# Main.net
KiCad netlist of a schematic drawn in Altium Designer
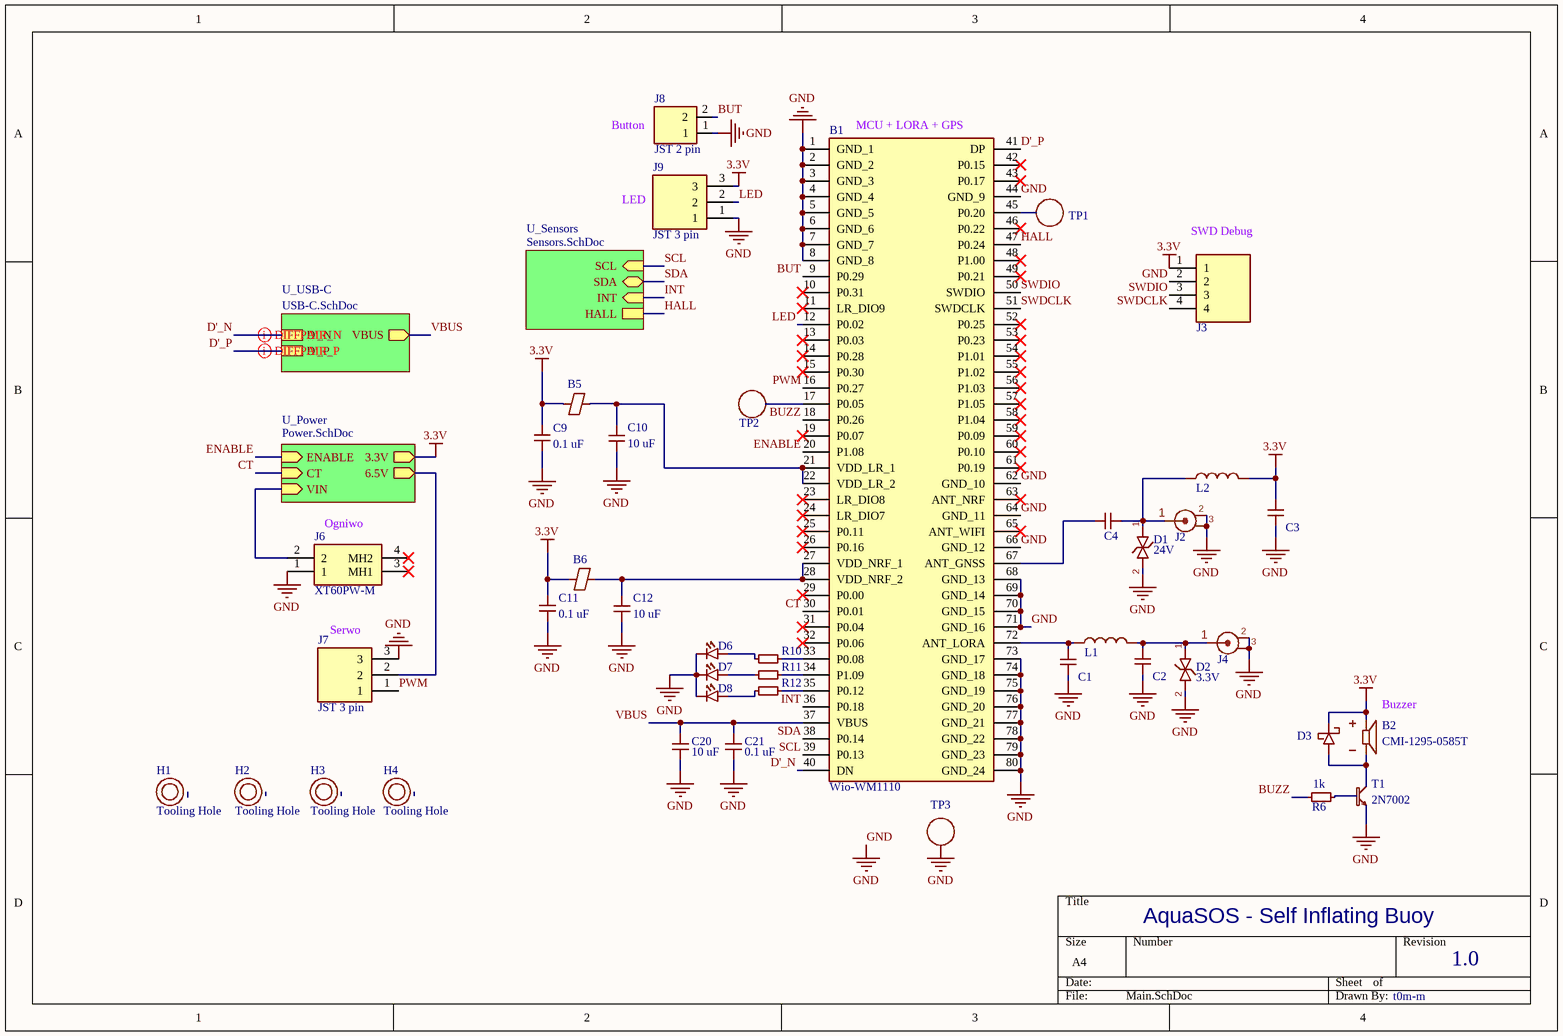
[diagram p0: Main.SchDoc]

(export (version "E")
  (design (tool "Eeschema 10.0.6"))
  (components
    (comp (ref "B1")
      (value "Wio-WM1110")
      (footprint "WioWM1110")
      (description "LoRa Wireless Module - Powered by Semtech")
      (libsource (lib "Schlib1") (part "Wio-WM1110"))
    )
    (comp (ref "B2")
      (value "CMI-1295-0585T")
      (footprint "CMI-1295-0585T")
      (description "Buzzer")
      (libsource (lib "Schlib1") (part "CMI-1295-0585T"))
    )
    (comp (ref "B5")
      (value "MPZ1608S121ATDH5")
      (footprint "MPZ1608S121ATDH5")
      (description "Ferrite Beads 0603 120ohms 2000mA Power Line AEC-Q200")
      (fields (field (name "MOUSER PART NUMBER") "810-MPZ1608S121ATDH5"))
      (libsource (lib "Schlib1") (part "MPZ1608S121ATDH5"))
    )
    (comp (ref "B6")
      (value "MPZ1608S121ATDH5")
      (footprint "MPZ1608S121ATDH5")
      (description "Ferrite Beads 0603 120ohms 2000mA Power Line AEC-Q200")
      (fields (field (name "MOUSER PART NUMBER") "810-MPZ1608S121ATDH5"))
      (libsource (lib "Schlib1") (part "MPZ1608S121ATDH5"))
    )
    (comp (ref "C1")
      (value "Capacitor")
      (footprint "KGM05CS60J106MH")
      (description "0402 SMD")
      (libsource (lib "AquaSOS DevBoard") (part "Capacitor"))
    )
    (comp (ref "C2")
      (value "Capacitor")
      (footprint "KGM05CS60J106MH")
      (description "0402 SMD")
      (libsource (lib "AquaSOS DevBoard") (part "Capacitor"))
    )
    (comp (ref "C3")
      (value "Capacitor")
      (footprint "KGM05CS60J106MH")
      (description "0402 SMD")
      (libsource (lib "AquaSOS DevBoard") (part "Capacitor"))
    )
    (comp (ref "C4")
      (value "Capacitor")
      (footprint "KGM05CS60J106MH")
      (description "0402 SMD")
      (libsource (lib "AquaSOS DevBoard") (part "Capacitor"))
    )
    (comp (ref "C9")
      (value "0.1 uF")
      (footprint "MLASU105SB7104KFNB25")
      (description "0.1uF Capacitor")
      (libsource (lib "Schlib1") (part "MLASU105SB7104KFNB25"))
    )
    (comp (ref "C10")
      (value "10 uF")
      (footprint "KGM05CS60J106MH")
      (description "10 uF Capacitor")
      (libsource (lib "Schlib1") (part "KGM05CS60J106MH"))
    )
    (comp (ref "C11")
      (value "0.1 uF")
      (footprint "MLASU105SB7104KFNB25")
      (description "0.1uF Capacitor")
      (libsource (lib "Schlib1") (part "MLASU105SB7104KFNB25"))
    )
    (comp (ref "C12")
      (value "10 uF")
      (footprint "KGM05CS60J106MH")
      (description "10 uF Capacitor")
      (libsource (lib "Schlib1") (part "KGM05CS60J106MH"))
    )
    (comp (ref "C20")
      (value "10 uF")
      (footprint "KGM05CS60J106MH")
      (description "10 uF Capacitor")
      (libsource (lib "AquaSOS DevBoard") (part "KGM05CS60J106MH"))
    )
    (comp (ref "C21")
      (value "0.1 uF")
      (footprint "MLASU105SB7104KFNB25")
      (description "0.1uF Capacitor")
      (libsource (lib "AquaSOS DevBoard") (part "MLASU105SB7104KFNB25"))
    )
    (comp (ref "D1")
      (value "24V")
      (footprint "RCLAMP2431TTCT")
      (description "ESD Suppressors / TVS Diodes LOW CAP/ESD CLAP, 1 LINE")
      (fields
        (field (name "MOUSER PART NUMBER") "947-RCLAMP2431T.TCT")
        (field (name "MANUFACTURER_PART_NUMBER") "RCLAMP2431T.TCT")
      )
      (libsource (lib "Schlib1") (part "RCLAMP2431T.TCT"))
    )
    (comp (ref "D2")
      (value "CPDV3V3A-HF")
      (footprint "CPDV3V3A-HF")
      (description "3.3 V, 0.4pF, Bidirectional")
      (libsource (lib "AquaSOS DevBoard") (part "CPDV3V3A-HF"))
    )
    (comp (ref "D3")
      (value "BAT5402VH6327XTSA1")
      (footprint "BAT5402VH6327XTSA1")
      (description "Schottky Diode")
      (libsource (lib "Schlib1") (part "BAT5402VH6327XTSA1"))
    )
    (comp (ref "D6")
      (value "APT1608SGC")
      (footprint "APT1608SGC")
      (description "0402 SMD LED")
      (libsource (lib "AquaSOS DevBoard") (part "APT1608SGC"))
    )
    (comp (ref "D7")
      (value "APT1608SGC")
      (footprint "APT1608SGC")
      (description "0402 SMD LED")
      (libsource (lib "AquaSOS DevBoard") (part "APT1608SGC"))
    )
    (comp (ref "D8")
      (value "APT1608SGC")
      (footprint "APT1608SGC")
      (description "0402 SMD LED")
      (libsource (lib "AquaSOS DevBoard") (part "APT1608SGC"))
    )
    (comp (ref "H1")
      (value "Tooling Hole")
      (footprint "Tooling Hole")
      (libsource (lib "AquaSOS DevBoard") (part "Tooling Hole"))
    )
    (comp (ref "H2")
      (value "Tooling Hole")
      (footprint "Tooling Hole")
      (libsource (lib "AquaSOS DevBoard") (part "Tooling Hole"))
    )
    (comp (ref "H3")
      (value "Tooling Hole")
      (footprint "Tooling Hole")
      (libsource (lib "AquaSOS DevBoard") (part "Tooling Hole"))
    )
    (comp (ref "H4")
      (value "Tooling Hole")
      (footprint "Tooling Hole")
      (libsource (lib "AquaSOS DevBoard") (part "Tooling Hole"))
    )
    (comp (ref "J2")
      (value "U.FL-R-SMT-1(10)")
      (footprint "HRS_U.FL-R-SMT-1(10)")
      (description "Antenna Connector")
      (libsource (lib "AquaSOS DevBoard") (part "U.FL-R-SMT-1(10)"))
    )
    (comp (ref "J3")
      (value "22-10-2041")
      (footprint "1x4 Goldpin Header")
      (description "Headers & Wire Housings VERT PCB HDR 4P GOLD PLATING")
      (fields (field (name "MOUSER PART NUMBER") "538-22-10-2041"))
      (libsource (lib "Schlib1") (part "1x4 Goldpin Header"))
    )
    (comp (ref "J4")
      (value "U.FL-R-SMT-1(10)")
      (footprint "HRS_U.FL-R-SMT-1(10)")
      (description "Antenna Connector")
      (libsource (lib "AquaSOS DevBoard") (part "U.FL-R-SMT-1(10)"))
    )
    (comp (ref "J6")
      (value "XT60PW-M")
      (footprint "XT60PWM")
      (description "Connector: DC supply; socket; XT60; male; PIN: 2; on PCBs; THT; 30A")
      (libsource (lib "Schlib1") (part "XT60PW-M"))
    )
    (comp (ref "J7")
      (value "JST 3 pin")
      (footprint "S3B-PH-K-S")
      (description "JST 3 pin connector")
      (libsource (lib "AquaSOS DevBoard") (part "JST 3 pin"))
    )
    (comp (ref "J8")
      (value "JST 2 pin")
      (footprint "JST_S2B-PH-K-S(LF)(SN)")
      (description "Connector Header Through Hole, Right Angle 2 position")
      (fields (field (name "MF") "JST Sales America Inc.") (field (name "MP") "S2B-PH-K-S(LF)(SN)"))
      (libsource (lib "AquaSOS DevBoard") (part "JST 2 pin"))
    )
    (comp (ref "J9")
      (value "JST 3 pin")
      (footprint "S3B-PH-K-S")
      (description "JST 3 pin connector")
      (libsource (lib "AquaSOS DevBoard") (part "JST 3 pin"))
    )
    (comp (ref "L1")
      (value "Inductor")
      (footprint "KGM05CS60J106MH")
      (libsource (lib "AquaSOS DevBoard") (part "Inductor"))
    )
    (comp (ref "L2")
      (value "Inductor")
      (footprint "KGM05CS60J106MH")
      (libsource (lib "AquaSOS DevBoard") (part "Inductor"))
    )
    (comp (ref "R6")
      (value "MR04X102 JTL")
      (footprint "MR04X102 JTL")
      (description "1k 0402 Resistor")
      (libsource (lib "Schlib1") (part "MR04X102 JTL"))
    )
    (comp (ref "R10")
      (value "300")
      (footprint "RC0402JR-075K1P")
      (libsource (lib "AquaSOS DevBoard") (part "CR0402-FX-3000GLF"))
    )
    (comp (ref "R11")
      (value "300")
      (footprint "RC0402JR-075K1P")
      (libsource (lib "AquaSOS DevBoard") (part "CR0402-FX-3000GLF"))
    )
    (comp (ref "R12")
      (value "300")
      (footprint "RC0402JR-075K1P")
      (libsource (lib "AquaSOS DevBoard") (part "CR0402-FX-3000GLF"))
    )
    (comp (ref "T1")
      (value "2N7002")
      (footprint "2N7002")
      (description "Transistor")
      (libsource (lib "Schlib1") (part "2N7002"))
    )
    (comp (ref "TP1")
      (value "TP")
      (footprint "Test Point")
      (description "Test Point")
      (libsource (lib "AquaSOS DevBoard") (part "Test Point"))
    )
    (comp (ref "TP2")
      (value "TP")
      (footprint "Test Point")
      (description "Test Point")
      (libsource (lib "AquaSOS DevBoard") (part "Test Point"))
    )
    (comp (ref "TP3")
      (value "TP")
      (footprint "Test Point")
      (description "Test Point")
      (libsource (lib "AquaSOS DevBoard") (part "Test Point"))
    )
  )
  (nets
    (net (code "1") (name "/6.5V") (class "Default")
      (node (ref "J7") (pin "2") (pinfunction "2_2") (pintype "passive"))
    )
    (net (code "2") (name "/BUT") (class "Default")
      (node (ref "B1") (pin "9") (pinfunction "P0.29_9") (pintype "passive"))
      (node (ref "J8") (pin "2") (pinfunction "2_2") (pintype "passive"))
    )
    (net (code "3") (name "/BUZZ") (class "Default")
      (node (ref "B1") (pin "18") (pinfunction "P0.26_18") (pintype "passive"))
      (node (ref "R6") (pin "1") (pinfunction "1_1") (pintype "passive"))
    )
    (net (code "4") (name "/CT") (class "Default")
      (node (ref "B1") (pin "30") (pinfunction "P0.01_30") (pintype "passive"))
    )
    (net (code "5") (name "/D'_N") (class "Default")
      (node (ref "B1") (pin "40") (pinfunction "DN_40") (pintype "passive"))
    )
    (net (code "6") (name "/D'_P") (class "Default")
      (node (ref "B1") (pin "41") (pinfunction "DP_41") (pintype "passive"))
    )
    (net (code "7") (name "/ENABLE") (class "Default")
      (node (ref "B1") (pin "20") (pinfunction "P1.08_20") (pintype "passive"))
    )
    (net (code "8") (name "/HALL") (class "Default")
      (node (ref "B1") (pin "47") (pinfunction "P0.24_47") (pintype "passive"))
    )
    (net (code "9") (name "/INT") (class "Default")
      (node (ref "B1") (pin "36") (pinfunction "P0.18_36") (pintype "passive"))
    )
    (net (code "10") (name "/LED") (class "Default")
      (node (ref "B1") (pin "12") (pinfunction "P0.02_12") (pintype "passive"))
      (node (ref "J9") (pin "2") (pinfunction "2_2") (pintype "passive"))
    )
    (net (code "11") (name "/PWM") (class "Default")
      (node (ref "B1") (pin "16") (pinfunction "P0.27_16") (pintype "passive"))
      (node (ref "J7") (pin "1") (pinfunction "1_1") (pintype "passive"))
    )
    (net (code "12") (name "/SCL") (class "Default")
      (node (ref "B1") (pin "39") (pinfunction "P0.13_39") (pintype "passive"))
    )
    (net (code "13") (name "/SDA") (class "Default")
      (node (ref "B1") (pin "38") (pinfunction "P0.14_38") (pintype "passive"))
    )
    (net (code "14") (name "/SWDCLK") (class "Default")
      (node (ref "B1") (pin "51") (pinfunction "SWDCLK_51") (pintype "passive"))
      (node (ref "J3") (pin "4") (pinfunction "4_4") (pintype "passive"))
    )
    (net (code "15") (name "/SWDIO") (class "Default")
      (node (ref "B1") (pin "50") (pinfunction "SWDIO_50") (pintype "passive"))
      (node (ref "J3") (pin "3") (pinfunction "3_3") (pintype "passive"))
    )
    (net (code "16") (name "/VBUS") (class "Default")
      (node (ref "B1") (pin "37") (pinfunction "VBUS_37") (pintype "passive"))
      (node (ref "C20") (pin "1") (pinfunction "1_1") (pintype "passive"))
      (node (ref "C21") (pin "1") (pinfunction "1_1") (pintype "passive"))
    )
    (net (code "17") (name "/VIN") (class "Default")
      (node (ref "J6") (pin "2") (pinfunction "2_2") (pintype "passive"))
    )
    (net (code "18") (name "3.3V") (class "Default")
      (node (ref "B2") (pin "P") (pinfunction "P_P") (pintype "passive"))
      (node (ref "B5") (pin "1") (pinfunction "1_1") (pintype "passive"))
      (node (ref "B6") (pin "1") (pinfunction "1_1") (pintype "passive"))
      (node (ref "C11") (pin "1") (pinfunction "1_1") (pintype "passive"))
      (node (ref "C3") (pin "1") (pinfunction "1_1") (pintype "passive"))
      (node (ref "C9") (pin "1") (pinfunction "1_1") (pintype "passive"))
      (node (ref "D3") (pin "2") (pinfunction "A_2") (pintype "passive"))
      (node (ref "J3") (pin "1") (pinfunction "1_1") (pintype "passive"))
      (node (ref "J9") (pin "3") (pinfunction "3_3") (pintype "passive"))
      (node (ref "L2") (pin "2") (pinfunction "2_2") (pintype "passive"))
    )
    (net (code "19") (name "GND") (class "Default")
      (node (ref "B1") (pin "1") (pinfunction "GND_1_1") (pintype "passive"))
      (node (ref "B1") (pin "2") (pinfunction "GND_2_2") (pintype "passive"))
      (node (ref "B1") (pin "3") (pinfunction "GND_3_3") (pintype "passive"))
      (node (ref "B1") (pin "4") (pinfunction "GND_4_4") (pintype "passive"))
      (node (ref "B1") (pin "44") (pinfunction "GND_9_44") (pintype "passive"))
      (node (ref "B1") (pin "5") (pinfunction "GND_5_5") (pintype "passive"))
      (node (ref "B1") (pin "6") (pinfunction "GND_6_6") (pintype "passive"))
      (node (ref "B1") (pin "62") (pinfunction "GND_10_62") (pintype "passive"))
      (node (ref "B1") (pin "64") (pinfunction "GND_11_64") (pintype "passive"))
      (node (ref "B1") (pin "66") (pinfunction "GND_12_66") (pintype "passive"))
      (node (ref "B1") (pin "68") (pinfunction "GND_13_68") (pintype "passive"))
      (node (ref "B1") (pin "69") (pinfunction "GND_14_69") (pintype "passive"))
      (node (ref "B1") (pin "7") (pinfunction "GND_7_7") (pintype "passive"))
      (node (ref "B1") (pin "70") (pinfunction "GND_15_70") (pintype "passive"))
      (node (ref "B1") (pin "71") (pinfunction "GND_16_71") (pintype "passive"))
      (node (ref "B1") (pin "73") (pinfunction "GND_17_73") (pintype "passive"))
      (node (ref "B1") (pin "74") (pinfunction "GND_18_74") (pintype "passive"))
      (node (ref "B1") (pin "75") (pinfunction "GND_19_75") (pintype "passive"))
      (node (ref "B1") (pin "76") (pinfunction "GND_20_76") (pintype "passive"))
      (node (ref "B1") (pin "77") (pinfunction "GND_21_77") (pintype "passive"))
      (node (ref "B1") (pin "78") (pinfunction "GND_22_78") (pintype "passive"))
      (node (ref "B1") (pin "79") (pinfunction "GND_23_79") (pintype "passive"))
      (node (ref "B1") (pin "8") (pinfunction "GND_8_8") (pintype "passive"))
      (node (ref "B1") (pin "80") (pinfunction "GND_24_80") (pintype "passive"))
      (node (ref "C1") (pin "2") (pinfunction "2_2") (pintype "passive"))
      (node (ref "C10") (pin "2") (pinfunction "2_2") (pintype "passive"))
      (node (ref "C11") (pin "2") (pinfunction "2_2") (pintype "passive"))
      (node (ref "C12") (pin "2") (pinfunction "2_2") (pintype "passive"))
      (node (ref "C2") (pin "2") (pinfunction "2_2") (pintype "passive"))
      (node (ref "C20") (pin "2") (pinfunction "2_2") (pintype "passive"))
      (node (ref "C21") (pin "2") (pinfunction "2_2") (pintype "passive"))
      (node (ref "C3") (pin "2") (pinfunction "2_2") (pintype "passive"))
      (node (ref "C9") (pin "2") (pinfunction "2_2") (pintype "passive"))
      (node (ref "D1") (pin "2") (pinfunction "A_2") (pintype "passive"))
      (node (ref "D2") (pin "2") (pinfunction "A_2") (pintype "passive"))
      (node (ref "D6") (pin "1") (pinfunction "K_1") (pintype "passive"))
      (node (ref "D7") (pin "1") (pinfunction "K_1") (pintype "passive"))
      (node (ref "D8") (pin "1") (pinfunction "K_1") (pintype "passive"))
      (node (ref "J2") (pin "2") (pinfunction "2_2") (pintype "passive"))
      (node (ref "J2") (pin "3") (pinfunction "3_3") (pintype "passive"))
      (node (ref "J3") (pin "2") (pinfunction "2_2") (pintype "passive"))
      (node (ref "J4") (pin "2") (pinfunction "2_2") (pintype "passive"))
      (node (ref "J4") (pin "3") (pinfunction "3_3") (pintype "passive"))
      (node (ref "J6") (pin "1") (pinfunction "1_1") (pintype "passive"))
      (node (ref "J7") (pin "3") (pinfunction "3_3") (pintype "passive"))
      (node (ref "J8") (pin "1") (pinfunction "1_1") (pintype "passive"))
      (node (ref "J9") (pin "1") (pinfunction "1_1") (pintype "passive"))
      (node (ref "T1") (pin "2") (pinfunction "S_2") (pintype "passive"))
      (node (ref "TP3") (pin "1") (pinfunction "1_1") (pintype "passive"))
    )
    (net (code "20") (name "Net-(B1-ANT_GNSS)") (class "Default")
      (node (ref "B1") (pin "67") (pinfunction "ANT_GNSS_67") (pintype "passive"))
      (node (ref "C4") (pin "1") (pinfunction "1_1") (pintype "passive"))
    )
    (net (code "21") (name "Net-(B1-ANT_LORA)") (class "Default")
      (node (ref "B1") (pin "72") (pinfunction "ANT_LORA_72") (pintype "passive"))
      (node (ref "C1") (pin "1") (pinfunction "1_1") (pintype "passive"))
      (node (ref "L1") (pin "1") (pinfunction "1_1") (pintype "passive"))
    )
    (net (code "22") (name "Net-(B1-P0.05)") (class "Default")
      (node (ref "B1") (pin "17") (pinfunction "P0.05_17") (pintype "passive"))
      (node (ref "TP2") (pin "1") (pinfunction "1_1") (pintype "passive"))
    )
    (net (code "23") (name "Net-(B1-P0.08)") (class "Default")
      (node (ref "B1") (pin "33") (pinfunction "P0.08_33") (pintype "passive"))
      (node (ref "R10") (pin "2") (pinfunction "2_2") (pintype "passive"))
    )
    (net (code "24") (name "Net-(B1-P0.12)") (class "Default")
      (node (ref "B1") (pin "35") (pinfunction "P0.12_35") (pintype "passive"))
      (node (ref "R12") (pin "2") (pinfunction "2_2") (pintype "passive"))
    )
    (net (code "25") (name "Net-(B1-P0.20)") (class "Default")
      (node (ref "B1") (pin "45") (pinfunction "P0.20_45") (pintype "passive"))
      (node (ref "TP1") (pin "1") (pinfunction "1_1") (pintype "passive"))
    )
    (net (code "26") (name "Net-(B1-P1.09)") (class "Default")
      (node (ref "B1") (pin "34") (pinfunction "P1.09_34") (pintype "passive"))
      (node (ref "R11") (pin "2") (pinfunction "2_2") (pintype "passive"))
    )
    (net (code "27") (name "Net-(B1-VDD_LR_1)") (class "Default")
      (node (ref "B1") (pin "21") (pinfunction "VDD_LR_1_21") (pintype "passive"))
      (node (ref "B1") (pin "22") (pinfunction "VDD_LR_2_22") (pintype "passive"))
      (node (ref "B5") (pin "2") (pinfunction "2_2") (pintype "passive"))
      (node (ref "C10") (pin "1") (pinfunction "1_1") (pintype "passive"))
    )
    (net (code "28") (name "Net-(B1-VDD_NRF_1)") (class "Default")
      (node (ref "B1") (pin "27") (pinfunction "VDD_NRF_1_27") (pintype "passive"))
      (node (ref "B1") (pin "28") (pinfunction "VDD_NRF_2_28") (pintype "passive"))
      (node (ref "B6") (pin "2") (pinfunction "2_2") (pintype "passive"))
      (node (ref "C12") (pin "1") (pinfunction "1_1") (pintype "passive"))
    )
    (net (code "29") (name "Net-(D1-K)") (class "Default")
      (node (ref "C4") (pin "2") (pinfunction "2_2") (pintype "passive"))
      (node (ref "D1") (pin "1") (pinfunction "K_1") (pintype "passive"))
      (node (ref "J2") (pin "1") (pinfunction "1_1") (pintype "passive"))
      (node (ref "L2") (pin "1") (pinfunction "1_1") (pintype "passive"))
    )
    (net (code "30") (name "Net-(D2-K)") (class "Default")
      (node (ref "C2") (pin "1") (pinfunction "1_1") (pintype "passive"))
      (node (ref "D2") (pin "1") (pinfunction "K_1") (pintype "passive"))
      (node (ref "J4") (pin "1") (pinfunction "1_1") (pintype "passive"))
      (node (ref "L1") (pin "2") (pinfunction "2_2") (pintype "passive"))
    )
    (net (code "31") (name "Net-(D3-K)") (class "Default")
      (node (ref "B2") (pin "N") (pinfunction "N_N") (pintype "passive"))
      (node (ref "D3") (pin "1") (pinfunction "K_1") (pintype "passive"))
      (node (ref "T1") (pin "3") (pinfunction "D_3") (pintype "passive"))
    )
    (net (code "32") (name "Net-(D6-A)") (class "Default")
      (node (ref "D6") (pin "2") (pinfunction "A_2") (pintype "passive"))
      (node (ref "R10") (pin "1") (pinfunction "1_1") (pintype "passive"))
    )
    (net (code "33") (name "Net-(D7-A)") (class "Default")
      (node (ref "D7") (pin "2") (pinfunction "A_2") (pintype "passive"))
      (node (ref "R11") (pin "1") (pinfunction "1_1") (pintype "passive"))
    )
    (net (code "34") (name "Net-(D8-A)") (class "Default")
      (node (ref "D8") (pin "2") (pinfunction "A_2") (pintype "passive"))
      (node (ref "R12") (pin "1") (pinfunction "1_1") (pintype "passive"))
    )
    (net (code "35") (name "Net-(T1-G)") (class "Default")
      (node (ref "R6") (pin "2") (pinfunction "2_2") (pintype "passive"))
      (node (ref "T1") (pin "1") (pinfunction "G_1") (pintype "passive"))
    )
    (net (code "36") (name "unconnected-(B1-ANT_NRF-Pad63)") (class "Default")
      (node (ref "B1") (pin "63") (pinfunction "ANT_NRF_63") (pintype "passive+no_connect"))
    )
    (net (code "37") (name "unconnected-(B1-ANT_WIFI-Pad65)") (class "Default")
      (node (ref "B1") (pin "65") (pinfunction "ANT_WIFI_65") (pintype "passive+no_connect"))
    )
    (net (code "38") (name "unconnected-(B1-LR_DIO7-Pad24)") (class "Default")
      (node (ref "B1") (pin "24") (pinfunction "LR_DIO7_24") (pintype "passive+no_connect"))
    )
    (net (code "39") (name "unconnected-(B1-LR_DIO8-Pad23)") (class "Default")
      (node (ref "B1") (pin "23") (pinfunction "LR_DIO8_23") (pintype "passive+no_connect"))
    )
    (net (code "40") (name "unconnected-(B1-LR_DIO9-Pad11)") (class "Default")
      (node (ref "B1") (pin "11") (pinfunction "LR_DIO9_11") (pintype "passive+no_connect"))
    )
    (net (code "41") (name "unconnected-(B1-P0.00-Pad29)") (class "Default")
      (node (ref "B1") (pin "29") (pinfunction "P0.00_29") (pintype "passive+no_connect"))
    )
    (net (code "42") (name "unconnected-(B1-P0.03-Pad13)") (class "Default")
      (node (ref "B1") (pin "13") (pinfunction "P0.03_13") (pintype "passive+no_connect"))
    )
    (net (code "43") (name "unconnected-(B1-P0.04-Pad31)") (class "Default")
      (node (ref "B1") (pin "31") (pinfunction "P0.04_31") (pintype "passive+no_connect"))
    )
    (net (code "44") (name "unconnected-(B1-P0.06-Pad32)") (class "Default")
      (node (ref "B1") (pin "32") (pinfunction "P0.06_32") (pintype "passive+no_connect"))
    )
    (net (code "45") (name "unconnected-(B1-P0.07-Pad19)") (class "Default")
      (node (ref "B1") (pin "19") (pinfunction "P0.07_19") (pintype "passive+no_connect"))
    )
    (net (code "46") (name "unconnected-(B1-P0.09-Pad59)") (class "Default")
      (node (ref "B1") (pin "59") (pinfunction "P0.09_59") (pintype "passive+no_connect"))
    )
    (net (code "47") (name "unconnected-(B1-P0.10-Pad60)") (class "Default")
      (node (ref "B1") (pin "60") (pinfunction "P0.10_60") (pintype "passive+no_connect"))
    )
    (net (code "48") (name "unconnected-(B1-P0.11-Pad25)") (class "Default")
      (node (ref "B1") (pin "25") (pinfunction "P0.11_25") (pintype "passive+no_connect"))
    )
    (net (code "49") (name "unconnected-(B1-P0.15-Pad42)") (class "Default")
      (node (ref "B1") (pin "42") (pinfunction "P0.15_42") (pintype "passive+no_connect"))
    )
    (net (code "50") (name "unconnected-(B1-P0.16-Pad26)") (class "Default")
      (node (ref "B1") (pin "26") (pinfunction "P0.16_26") (pintype "passive+no_connect"))
    )
    (net (code "51") (name "unconnected-(B1-P0.17-Pad43)") (class "Default")
      (node (ref "B1") (pin "43") (pinfunction "P0.17_43") (pintype "passive+no_connect"))
    )
    (net (code "52") (name "unconnected-(B1-P0.19-Pad61)") (class "Default")
      (node (ref "B1") (pin "61") (pinfunction "P0.19_61") (pintype "passive+no_connect"))
    )
    (net (code "53") (name "unconnected-(B1-P0.21-Pad49)") (class "Default")
      (node (ref "B1") (pin "49") (pinfunction "P0.21_49") (pintype "passive+no_connect"))
    )
    (net (code "54") (name "unconnected-(B1-P0.22-Pad46)") (class "Default")
      (node (ref "B1") (pin "46") (pinfunction "P0.22_46") (pintype "passive+no_connect"))
    )
    (net (code "55") (name "unconnected-(B1-P0.23-Pad53)") (class "Default")
      (node (ref "B1") (pin "53") (pinfunction "P0.23_53") (pintype "passive+no_connect"))
    )
    (net (code "56") (name "unconnected-(B1-P0.25-Pad52)") (class "Default")
      (node (ref "B1") (pin "52") (pinfunction "P0.25_52") (pintype "passive+no_connect"))
    )
    (net (code "57") (name "unconnected-(B1-P0.28-Pad14)") (class "Default")
      (node (ref "B1") (pin "14") (pinfunction "P0.28_14") (pintype "passive+no_connect"))
    )
    (net (code "58") (name "unconnected-(B1-P0.30-Pad15)") (class "Default")
      (node (ref "B1") (pin "15") (pinfunction "P0.30_15") (pintype "passive+no_connect"))
    )
    (net (code "59") (name "unconnected-(B1-P0.31-Pad10)") (class "Default")
      (node (ref "B1") (pin "10") (pinfunction "P0.31_10") (pintype "passive+no_connect"))
    )
    (net (code "60") (name "unconnected-(B1-P1.00-Pad48)") (class "Default")
      (node (ref "B1") (pin "48") (pinfunction "P1.00_48") (pintype "passive+no_connect"))
    )
    (net (code "61") (name "unconnected-(B1-P1.01-Pad54)") (class "Default")
      (node (ref "B1") (pin "54") (pinfunction "P1.01_54") (pintype "passive+no_connect"))
    )
    (net (code "62") (name "unconnected-(B1-P1.02-Pad55)") (class "Default")
      (node (ref "B1") (pin "55") (pinfunction "P1.02_55") (pintype "passive+no_connect"))
    )
    (net (code "63") (name "unconnected-(B1-P1.03-Pad56)") (class "Default")
      (node (ref "B1") (pin "56") (pinfunction "P1.03_56") (pintype "passive+no_connect"))
    )
    (net (code "64") (name "unconnected-(B1-P1.04-Pad58)") (class "Default")
      (node (ref "B1") (pin "58") (pinfunction "P1.04_58") (pintype "passive+no_connect"))
    )
    (net (code "65") (name "unconnected-(B1-P1.05-Pad57)") (class "Default")
      (node (ref "B1") (pin "57") (pinfunction "P1.05_57") (pintype "passive+no_connect"))
    )
    (net (code "66") (name "unconnected-(J6-MH1-Pad3)") (class "Default")
      (node (ref "J6") (pin "3") (pinfunction "MH1_3") (pintype "passive+no_connect"))
    )
    (net (code "67") (name "unconnected-(J6-MH2-Pad4)") (class "Default")
      (node (ref "J6") (pin "4") (pinfunction "MH2_4") (pintype "passive+no_connect"))
    )
  )
)
